# Linkable_LED_Matrix_Thru_Full_Mount.net
KiCad netlist of a schematic drawn in EAGLE
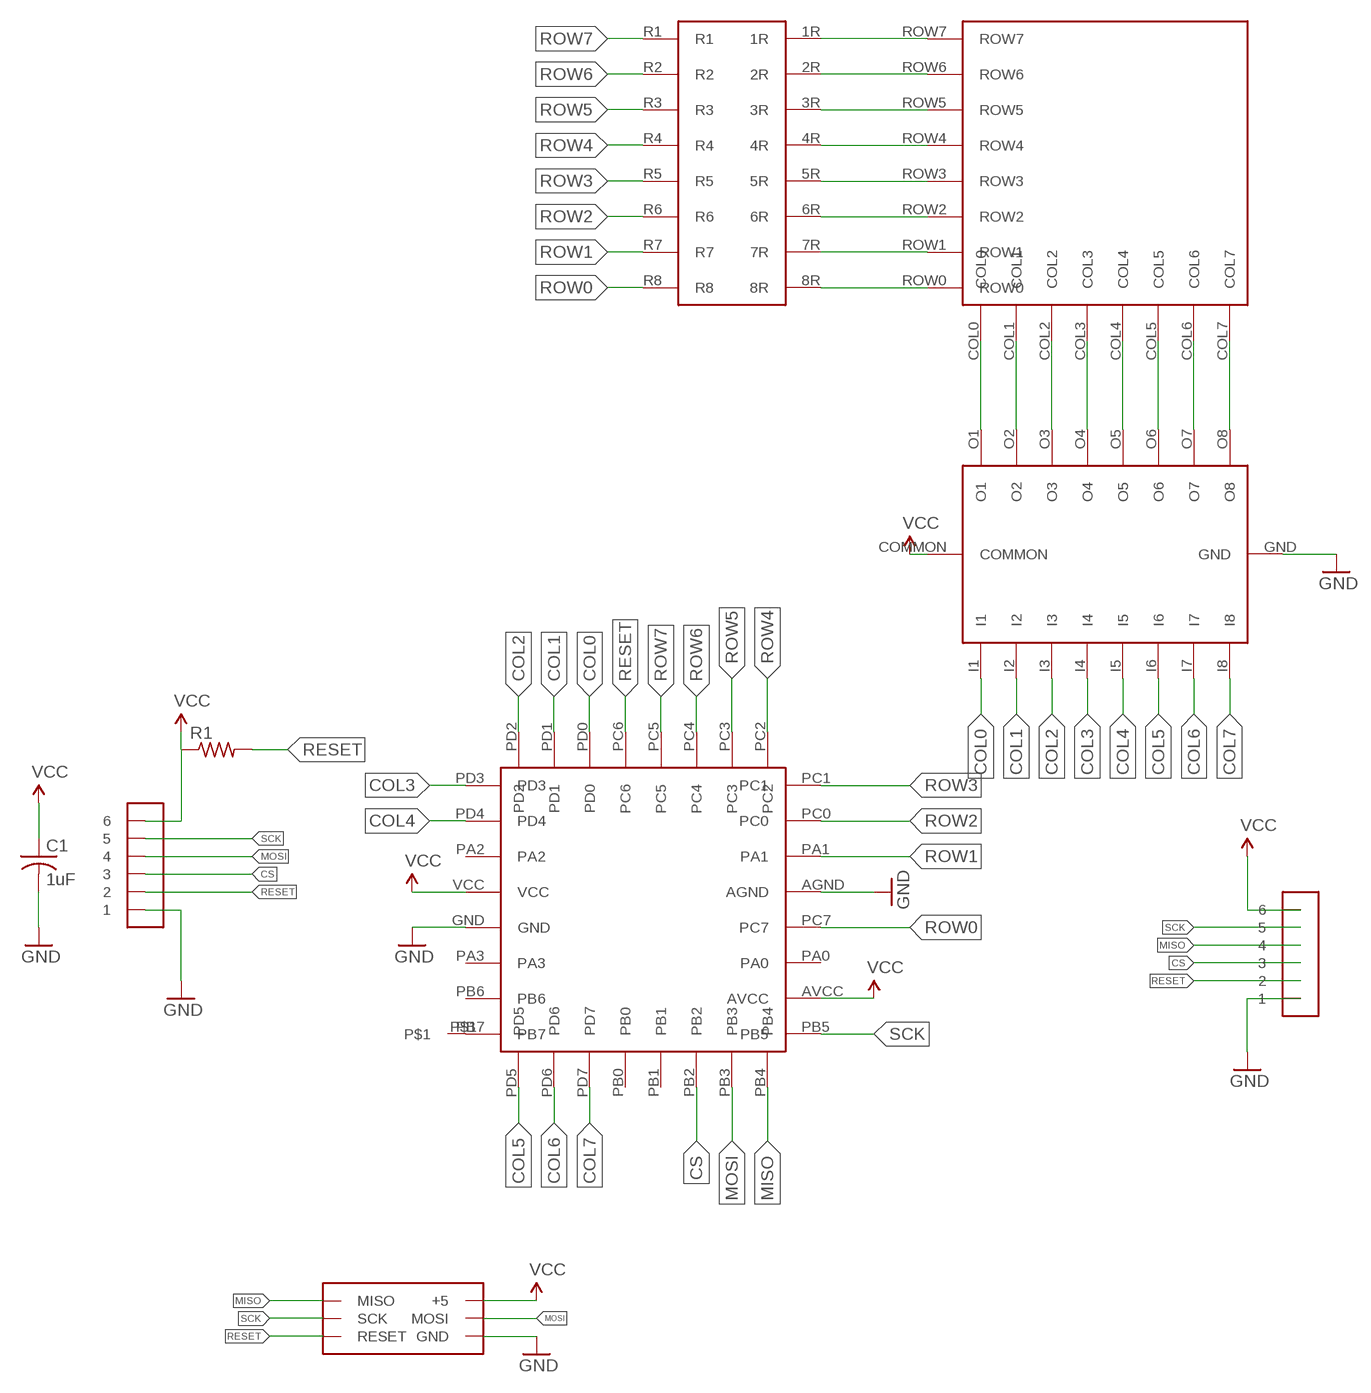
[diagram p0: schematic, sheet 1]

(export (version "E")
  (design (tool "Eeschema 10.0.6"))
  (components
    (comp (ref "C1")
      (value "1uF")
      (footprint "eagle-import:C0603")
      (libsource (lib "eagle-import") (part "C-USC0603"))
    )
    (comp (ref "R1")
      (value "R-US_R0603")
      (footprint "eagle-import:R0603")
      (libsource (lib "eagle-import") (part "R-US_R0603"))
    )
    (comp (ref "U$1")
      (value "ATTINY48")
      (footprint "eagle-import:ATTINY48")
      (libsource (lib "eagle-import") (part "ATTINY48"))
    )
    (comp (ref "U$2")
      (value "ULN2803AFWG")
      (footprint "eagle-import:ULN2803AFWG")
      (libsource (lib "eagle-import") (part "ULN2803AFWG"))
    )
    (comp (ref "U$3")
      (value "8X8_LED_MATRIX")
      (footprint "eagle-import:8X8_LED_MATRIX")
      (libsource (lib "eagle-import") (part "8X8_LED_MATRIX"))
    )
    (comp (ref "U$4")
      (value "RES_ARRAY")
      (footprint "eagle-import:RES_ARRAY")
      (libsource (lib "eagle-import") (part "RES_ARRAY"))
    )
    (comp (ref "U$5")
      (value "1X1MM_PAD")
      (footprint "eagle-import:1X1MM_PAD")
      (libsource (lib "eagle-import") (part "1X1MM_PAD"))
    )
    (comp (ref "U$6")
      (value "DIP1X6MALE")
      (footprint "eagle-import:DIP1X6MALE")
      (libsource (lib "eagle-import") (part "DIP1X6MALE"))
    )
    (comp (ref "U$7")
      (value "DIP1X6MALE")
      (footprint "eagle-import:DIP1X6MALE")
      (libsource (lib "eagle-import") (part "DIP1X6MALE"))
    )
    (comp (ref "U$9")
      (value "DIP2X3MALE")
      (footprint "eagle-import:DIP2X3MALE")
      (libsource (lib "eagle-import") (part "DIP2X3MALE"))
    )
  )
  (nets
    (net (code "1") (name "COL0") (class "Default")
      (node (ref "U$1") (pin "PD0") (pinfunction "PD0_PD0") (pintype "bidirectional"))
      (node (ref "U$2") (pin "I1") (pinfunction "I1_I1") (pintype "bidirectional"))
    )
    (net (code "2") (name "COL1") (class "Default")
      (node (ref "U$1") (pin "PD1") (pinfunction "PD1_PD1") (pintype "bidirectional"))
      (node (ref "U$2") (pin "I2") (pinfunction "I2_I2") (pintype "bidirectional"))
    )
    (net (code "3") (name "COL2") (class "Default")
      (node (ref "U$1") (pin "PD2") (pinfunction "PD2_PD2") (pintype "bidirectional"))
      (node (ref "U$2") (pin "I3") (pinfunction "I3_I3") (pintype "bidirectional"))
    )
    (net (code "4") (name "COL3") (class "Default")
      (node (ref "U$1") (pin "PD3") (pinfunction "PD3_PD3") (pintype "bidirectional"))
      (node (ref "U$2") (pin "I4") (pinfunction "I4_I4") (pintype "bidirectional"))
    )
    (net (code "5") (name "COL4") (class "Default")
      (node (ref "U$1") (pin "PD4") (pinfunction "PD4_PD4") (pintype "bidirectional"))
      (node (ref "U$2") (pin "I5") (pinfunction "I5_I5") (pintype "bidirectional"))
    )
    (net (code "6") (name "COL5") (class "Default")
      (node (ref "U$1") (pin "PD5") (pinfunction "PD5_PD5") (pintype "bidirectional"))
      (node (ref "U$2") (pin "I6") (pinfunction "I6_I6") (pintype "bidirectional"))
    )
    (net (code "7") (name "COL6") (class "Default")
      (node (ref "U$1") (pin "PD6") (pinfunction "PD6_PD6") (pintype "bidirectional"))
      (node (ref "U$2") (pin "I7") (pinfunction "I7_I7") (pintype "bidirectional"))
    )
    (net (code "8") (name "COL7") (class "Default")
      (node (ref "U$1") (pin "PD7") (pinfunction "PD7_PD7") (pintype "bidirectional"))
      (node (ref "U$2") (pin "I8") (pinfunction "I8_I8") (pintype "bidirectional"))
    )
    (net (code "9") (name "CS") (class "Default")
      (node (ref "U$1") (pin "PB2") (pinfunction "PB2_PB2") (pintype "bidirectional"))
      (node (ref "U$6") (pin "3") (pinfunction "3_3") (pintype "bidirectional"))
      (node (ref "U$7") (pin "3") (pinfunction "3_3") (pintype "bidirectional"))
    )
    (net (code "10") (name "GND") (class "Default")
      (node (ref "C1") (pin "2") (pinfunction "2_2") (pintype "passive"))
      (node (ref "U$1") (pin "AGND") (pinfunction "AGND_AGND") (pintype "bidirectional"))
      (node (ref "U$1") (pin "GND") (pinfunction "GND_GND") (pintype "bidirectional"))
      (node (ref "U$2") (pin "GND") (pinfunction "GND_GND") (pintype "bidirectional"))
      (node (ref "U$6") (pin "1") (pinfunction "1_1") (pintype "bidirectional"))
      (node (ref "U$7") (pin "1") (pinfunction "1_1") (pintype "bidirectional"))
      (node (ref "U$9") (pin "GND") (pinfunction "GND_GND") (pintype "bidirectional"))
    )
    (net (code "11") (name "MISO") (class "Default")
      (node (ref "U$1") (pin "PB4") (pinfunction "PB4_PB4") (pintype "bidirectional"))
      (node (ref "U$7") (pin "4") (pinfunction "4_4") (pintype "bidirectional"))
      (node (ref "U$9") (pin "MISO") (pinfunction "MISO_MISO") (pintype "bidirectional"))
    )
    (net (code "12") (name "MOSI") (class "Default")
      (node (ref "U$1") (pin "PB3") (pinfunction "PB3_PB3") (pintype "bidirectional"))
      (node (ref "U$6") (pin "4") (pinfunction "4_4") (pintype "bidirectional"))
      (node (ref "U$9") (pin "MOSI") (pinfunction "MOSI_MOSI") (pintype "bidirectional"))
    )
    (net (code "13") (name "Net-(U$1-PadPB7)") (class "Default")
      (node (ref "U$1") (pin "PB7") (pinfunction "PB7_PB7") (pintype "bidirectional"))
      (node (ref "U$5") (pin "P$1") (pinfunction "P$1_P$1") (pintype "bidirectional"))
    )
    (net (code "14") (name "Net-(U$2-PadO1)") (class "Default")
      (node (ref "U$2") (pin "O1") (pinfunction "O1_O1") (pintype "bidirectional"))
      (node (ref "U$3") (pin "COL0") (pinfunction "COL0_COL0") (pintype "bidirectional"))
    )
    (net (code "15") (name "Net-(U$2-PadO2)") (class "Default")
      (node (ref "U$2") (pin "O2") (pinfunction "O2_O2") (pintype "bidirectional"))
      (node (ref "U$3") (pin "COL1") (pinfunction "COL1_COL1") (pintype "bidirectional"))
    )
    (net (code "16") (name "Net-(U$2-PadO3)") (class "Default")
      (node (ref "U$2") (pin "O3") (pinfunction "O3_O3") (pintype "bidirectional"))
      (node (ref "U$3") (pin "COL2") (pinfunction "COL2_COL2") (pintype "bidirectional"))
    )
    (net (code "17") (name "Net-(U$2-PadO4)") (class "Default")
      (node (ref "U$2") (pin "O4") (pinfunction "O4_O4") (pintype "bidirectional"))
      (node (ref "U$3") (pin "COL3") (pinfunction "COL3_COL3") (pintype "bidirectional"))
    )
    (net (code "18") (name "Net-(U$2-PadO5)") (class "Default")
      (node (ref "U$2") (pin "O5") (pinfunction "O5_O5") (pintype "bidirectional"))
      (node (ref "U$3") (pin "COL4") (pinfunction "COL4_COL4") (pintype "bidirectional"))
    )
    (net (code "19") (name "Net-(U$2-PadO6)") (class "Default")
      (node (ref "U$2") (pin "O6") (pinfunction "O6_O6") (pintype "bidirectional"))
      (node (ref "U$3") (pin "COL5") (pinfunction "COL5_COL5") (pintype "bidirectional"))
    )
    (net (code "20") (name "Net-(U$2-PadO7)") (class "Default")
      (node (ref "U$2") (pin "O7") (pinfunction "O7_O7") (pintype "bidirectional"))
      (node (ref "U$3") (pin "COL6") (pinfunction "COL6_COL6") (pintype "bidirectional"))
    )
    (net (code "21") (name "Net-(U$2-PadO8)") (class "Default")
      (node (ref "U$2") (pin "O8") (pinfunction "O8_O8") (pintype "bidirectional"))
      (node (ref "U$3") (pin "COL7") (pinfunction "COL7_COL7") (pintype "bidirectional"))
    )
    (net (code "22") (name "Net-(U$3-PadROW0)") (class "Default")
      (node (ref "U$3") (pin "ROW0") (pinfunction "ROW0_ROW0") (pintype "bidirectional"))
      (node (ref "U$4") (pin "8R") (pinfunction "8R_8R") (pintype "bidirectional"))
    )
    (net (code "23") (name "Net-(U$3-PadROW1)") (class "Default")
      (node (ref "U$3") (pin "ROW1") (pinfunction "ROW1_ROW1") (pintype "bidirectional"))
      (node (ref "U$4") (pin "7R") (pinfunction "7R_7R") (pintype "bidirectional"))
    )
    (net (code "24") (name "Net-(U$3-PadROW2)") (class "Default")
      (node (ref "U$3") (pin "ROW2") (pinfunction "ROW2_ROW2") (pintype "bidirectional"))
      (node (ref "U$4") (pin "6R") (pinfunction "6R_6R") (pintype "bidirectional"))
    )
    (net (code "25") (name "Net-(U$3-PadROW3)") (class "Default")
      (node (ref "U$3") (pin "ROW3") (pinfunction "ROW3_ROW3") (pintype "bidirectional"))
      (node (ref "U$4") (pin "5R") (pinfunction "5R_5R") (pintype "bidirectional"))
    )
    (net (code "26") (name "Net-(U$3-PadROW4)") (class "Default")
      (node (ref "U$3") (pin "ROW4") (pinfunction "ROW4_ROW4") (pintype "bidirectional"))
      (node (ref "U$4") (pin "4R") (pinfunction "4R_4R") (pintype "bidirectional"))
    )
    (net (code "27") (name "Net-(U$3-PadROW5)") (class "Default")
      (node (ref "U$3") (pin "ROW5") (pinfunction "ROW5_ROW5") (pintype "bidirectional"))
      (node (ref "U$4") (pin "3R") (pinfunction "3R_3R") (pintype "bidirectional"))
    )
    (net (code "28") (name "Net-(U$3-PadROW6)") (class "Default")
      (node (ref "U$3") (pin "ROW6") (pinfunction "ROW6_ROW6") (pintype "bidirectional"))
      (node (ref "U$4") (pin "2R") (pinfunction "2R_2R") (pintype "bidirectional"))
    )
    (net (code "29") (name "Net-(U$3-PadROW7)") (class "Default")
      (node (ref "U$3") (pin "ROW7") (pinfunction "ROW7_ROW7") (pintype "bidirectional"))
      (node (ref "U$4") (pin "1R") (pinfunction "1R_1R") (pintype "bidirectional"))
    )
    (net (code "30") (name "RESET") (class "Default")
      (node (ref "R1") (pin "2") (pinfunction "2_2") (pintype "passive"))
      (node (ref "U$1") (pin "PC6") (pinfunction "PC6_PC6") (pintype "bidirectional"))
      (node (ref "U$6") (pin "2") (pinfunction "2_2") (pintype "bidirectional"))
      (node (ref "U$7") (pin "2") (pinfunction "2_2") (pintype "bidirectional"))
      (node (ref "U$9") (pin "RESET") (pinfunction "RESET_RESET") (pintype "bidirectional"))
    )
    (net (code "31") (name "ROW0") (class "Default")
      (node (ref "U$1") (pin "PC7") (pinfunction "PC7_PC7") (pintype "bidirectional"))
      (node (ref "U$4") (pin "R8") (pinfunction "R8_R8") (pintype "bidirectional"))
    )
    (net (code "32") (name "ROW1") (class "Default")
      (node (ref "U$1") (pin "PA1") (pinfunction "PA1_PA1") (pintype "bidirectional"))
      (node (ref "U$4") (pin "R7") (pinfunction "R7_R7") (pintype "bidirectional"))
    )
    (net (code "33") (name "ROW2") (class "Default")
      (node (ref "U$1") (pin "PC0") (pinfunction "PC0_PC0") (pintype "bidirectional"))
      (node (ref "U$4") (pin "R6") (pinfunction "R6_R6") (pintype "bidirectional"))
    )
    (net (code "34") (name "ROW3") (class "Default")
      (node (ref "U$1") (pin "PC1") (pinfunction "PC1_PC1") (pintype "bidirectional"))
      (node (ref "U$4") (pin "R5") (pinfunction "R5_R5") (pintype "bidirectional"))
    )
    (net (code "35") (name "ROW4") (class "Default")
      (node (ref "U$1") (pin "PC2") (pinfunction "PC2_PC2") (pintype "bidirectional"))
      (node (ref "U$4") (pin "R4") (pinfunction "R4_R4") (pintype "bidirectional"))
    )
    (net (code "36") (name "ROW5") (class "Default")
      (node (ref "U$1") (pin "PC3") (pinfunction "PC3_PC3") (pintype "bidirectional"))
      (node (ref "U$4") (pin "R3") (pinfunction "R3_R3") (pintype "bidirectional"))
    )
    (net (code "37") (name "ROW6") (class "Default")
      (node (ref "U$1") (pin "PC4") (pinfunction "PC4_PC4") (pintype "bidirectional"))
      (node (ref "U$4") (pin "R2") (pinfunction "R2_R2") (pintype "bidirectional"))
    )
    (net (code "38") (name "ROW7") (class "Default")
      (node (ref "U$1") (pin "PC5") (pinfunction "PC5_PC5") (pintype "bidirectional"))
      (node (ref "U$4") (pin "R1") (pinfunction "R1_R1") (pintype "bidirectional"))
    )
    (net (code "39") (name "SCK") (class "Default")
      (node (ref "U$1") (pin "PB5") (pinfunction "PB5_PB5") (pintype "bidirectional"))
      (node (ref "U$6") (pin "5") (pinfunction "5_5") (pintype "bidirectional"))
      (node (ref "U$7") (pin "5") (pinfunction "5_5") (pintype "bidirectional"))
      (node (ref "U$9") (pin "SCK") (pinfunction "SCK_SCK") (pintype "bidirectional"))
    )
    (net (code "40") (name "VCC") (class "Default")
      (node (ref "C1") (pin "1") (pinfunction "1_1") (pintype "passive"))
      (node (ref "R1") (pin "1") (pinfunction "1_1") (pintype "passive"))
      (node (ref "U$1") (pin "AVCC") (pinfunction "AVCC_AVCC") (pintype "bidirectional"))
      (node (ref "U$1") (pin "VCC") (pinfunction "VCC_VCC") (pintype "bidirectional"))
      (node (ref "U$2") (pin "COMMON") (pinfunction "COMMON_COMMON") (pintype "bidirectional"))
      (node (ref "U$6") (pin "6") (pinfunction "6_6") (pintype "bidirectional"))
      (node (ref "U$7") (pin "6") (pinfunction "6_6") (pintype "bidirectional"))
      (node (ref "U$9") (pin "5V") (pinfunction "+5_5V") (pintype "bidirectional"))
    )
    (net (code "41") (name "unconnected-(U$1-PadPA0)") (class "Default")
      (node (ref "U$1") (pin "PA0") (pinfunction "PA0_PA0") (pintype "bidirectional"))
    )
    (net (code "42") (name "unconnected-(U$1-PadPA2)") (class "Default")
      (node (ref "U$1") (pin "PA2") (pinfunction "PA2_PA2") (pintype "bidirectional"))
    )
    (net (code "43") (name "unconnected-(U$1-PadPA3)") (class "Default")
      (node (ref "U$1") (pin "PA3") (pinfunction "PA3_PA3") (pintype "bidirectional"))
    )
    (net (code "44") (name "unconnected-(U$1-PadPB0)") (class "Default")
      (node (ref "U$1") (pin "PB0") (pinfunction "PB0_PB0") (pintype "bidirectional"))
    )
    (net (code "45") (name "unconnected-(U$1-PadPB1)") (class "Default")
      (node (ref "U$1") (pin "PB1") (pinfunction "PB1_PB1") (pintype "bidirectional"))
    )
    (net (code "46") (name "unconnected-(U$1-PadPB6)") (class "Default")
      (node (ref "U$1") (pin "PB6") (pinfunction "PB6_PB6") (pintype "bidirectional"))
    )
  )
)
